# S7CAS-PLEIADES-CARTE-MERE_P20_FPGA-Decou.net
KiCad netlist of a schematic drawn in Altium Designer
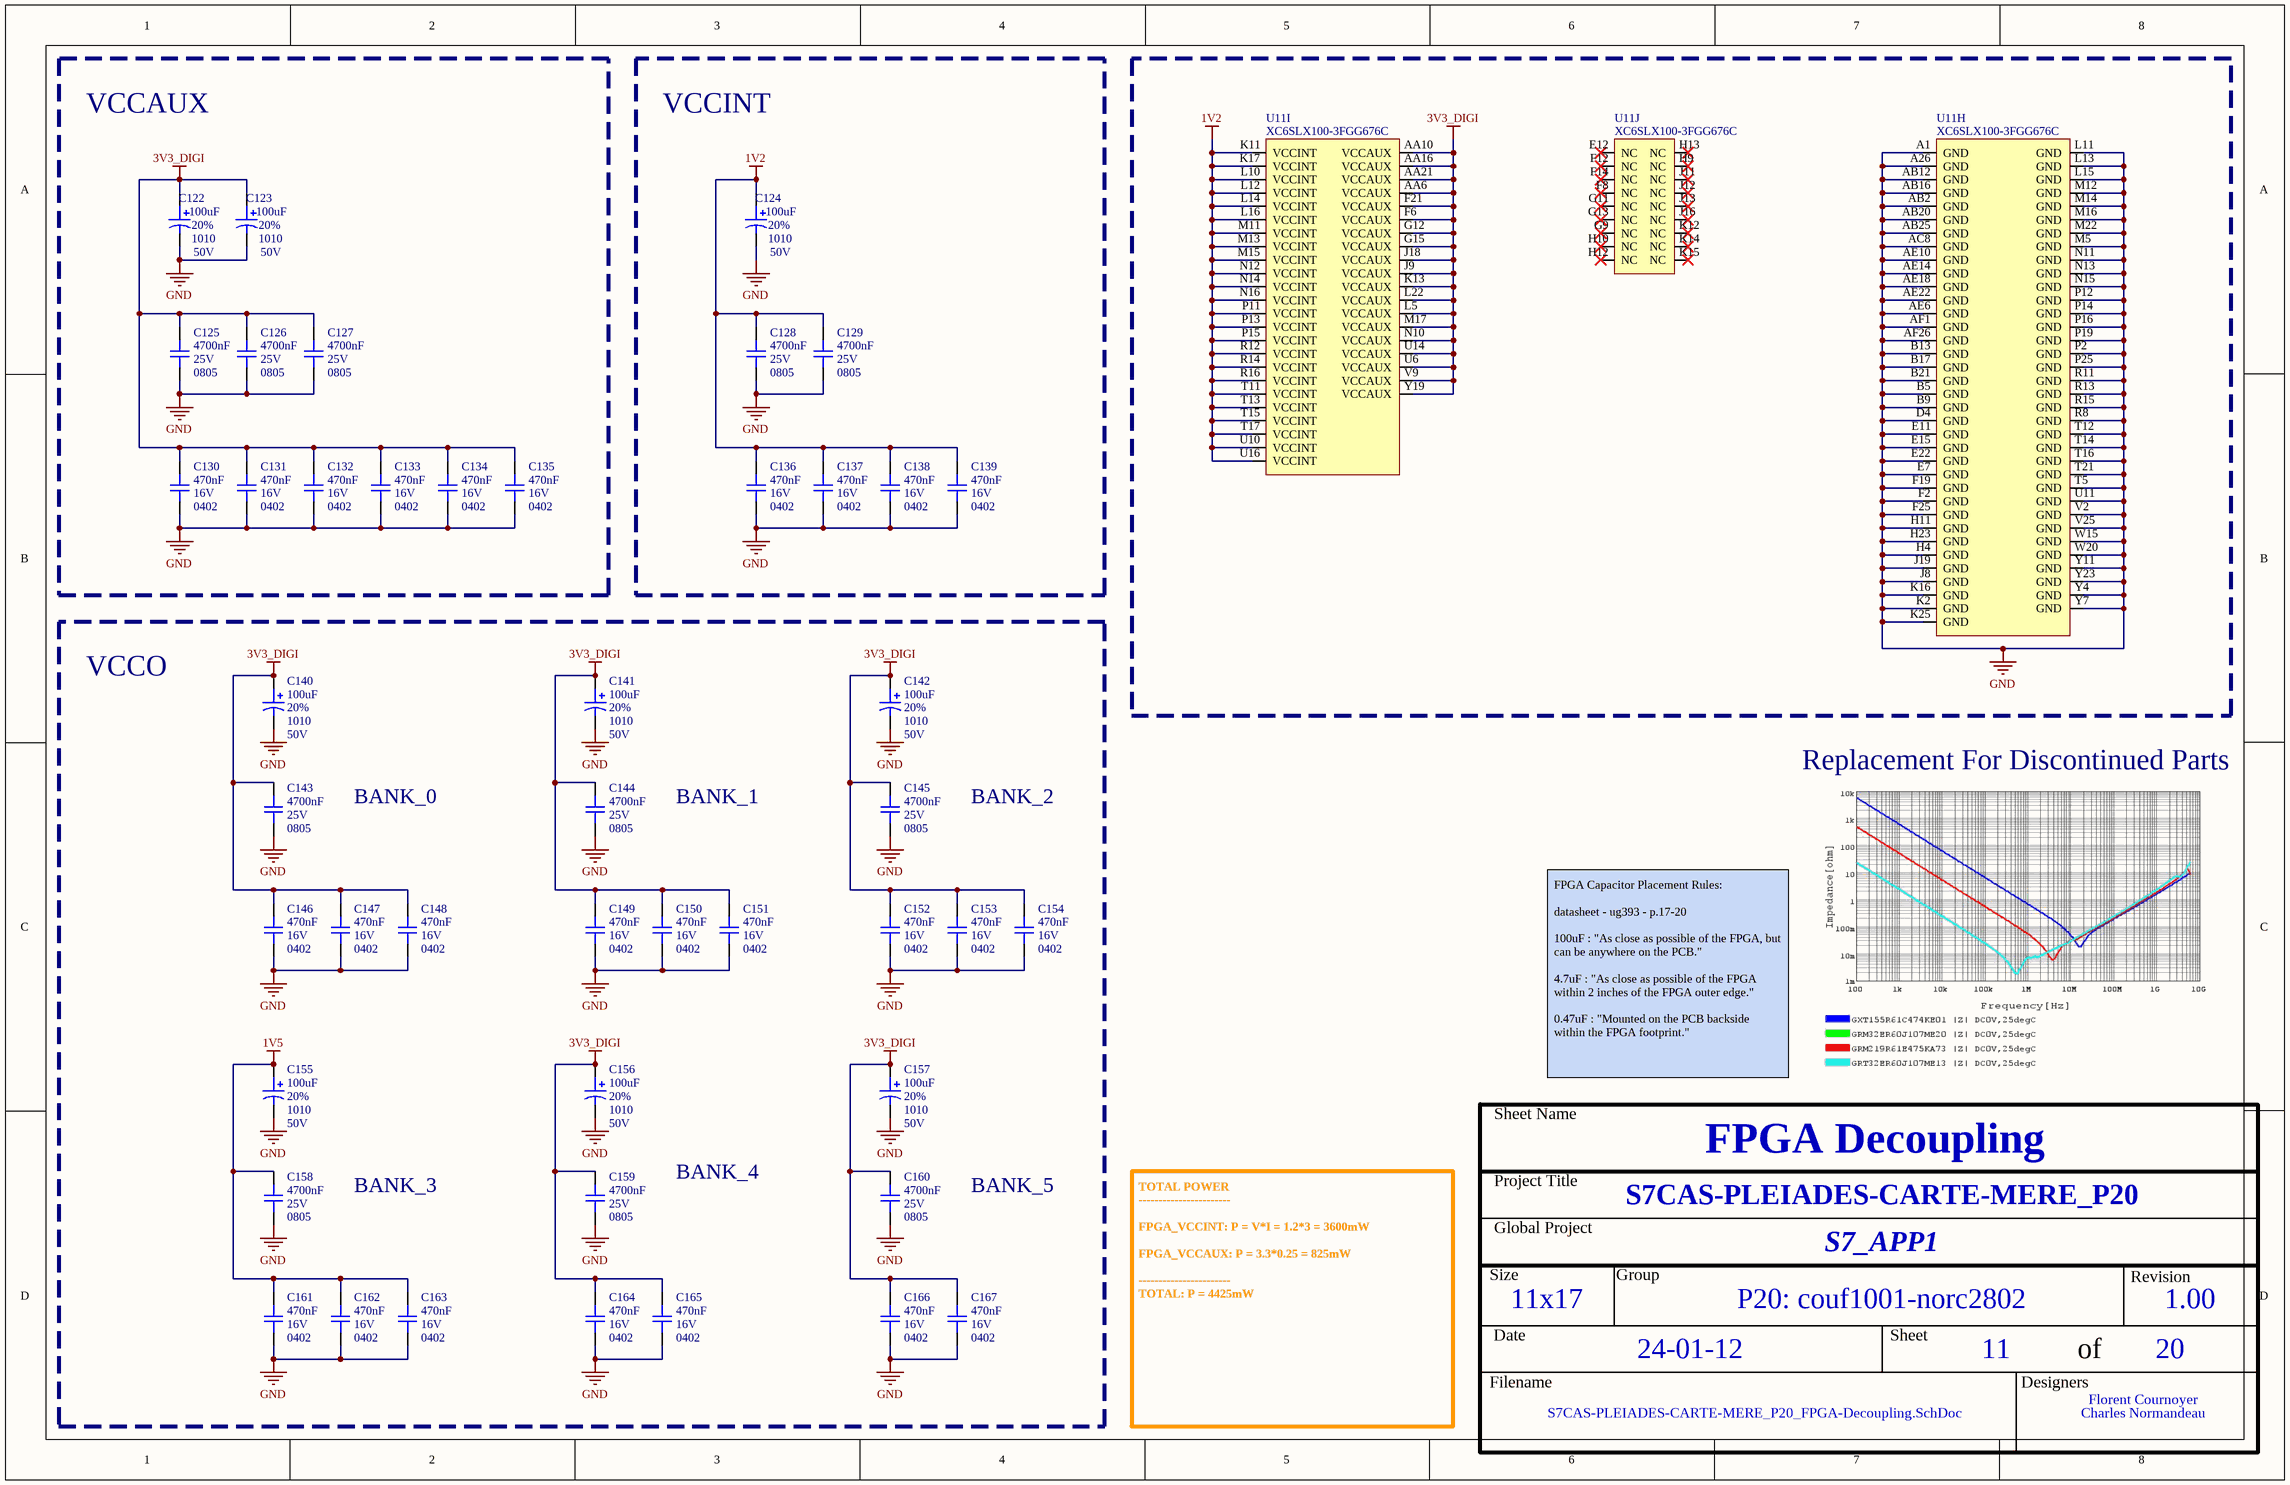
[diagram p0: S7CAS-PLEIADES-CARTE-MERE_P20_FPGA-Decoupling.SchDoc]

(export (version "E")
  (design (tool "Eeschema 10.0.6"))
  (components
    (comp (ref "C122")
      (value "100uF")
      (footprint "CAP_ALU_1010_vishay")
      (description "CAP - ALU 100uF 20% 50V - 1010")
      (fields
        (field (name "MFG") "Vishay Dale")
        (field (name "MFG PART NUMBER") "MAL215099101E3")
        (field (name "VOLTAGE") "50V")
        (field (name "PACKAGE") "1010")
        (field (name "PRECISION") "20%")
        (field (name "CREATEDBY") "Jonathan Bouchard")
      )
      (libsource (lib "S7CAS_LIB2023") (part "CAP_ALU_MAL215099101E3"))
    )
    (comp (ref "C123")
      (value "100uF")
      (footprint "CAP_ALU_1010_vishay")
      (description "CAP - ALU 100uF 20% 50V - 1010")
      (fields
        (field (name "MFG") "Vishay Dale")
        (field (name "MFG PART NUMBER") "MAL215099101E3")
        (field (name "VOLTAGE") "50V")
        (field (name "PACKAGE") "1010")
        (field (name "PRECISION") "20%")
        (field (name "CREATEDBY") "Jonathan Bouchard")
      )
      (libsource (lib "S7CAS_LIB2023") (part "CAP_ALU_MAL215099101E3"))
    )
    (comp (ref "C124")
      (value "100uF")
      (footprint "CAP_ALU_1010_vishay")
      (description "CAP - ALU 100uF 20% 50V - 1010")
      (fields
        (field (name "MFG") "Vishay Dale")
        (field (name "MFG PART NUMBER") "MAL215099101E3")
        (field (name "VOLTAGE") "50V")
        (field (name "PACKAGE") "1010")
        (field (name "PRECISION") "20%")
        (field (name "CREATEDBY") "Jonathan Bouchard")
      )
      (libsource (lib "S7CAS_LIB2023") (part "CAP_ALU_MAL215099101E3"))
    )
    (comp (ref "C125")
      (value "4700nF")
      (footprint "CAP_0805")
      (description "CAP - 0805")
      (fields
        (field (name "MFG PART NUMBER") "GRM219R61E475KA73")
        (field (name "VOLTAGE") "25V")
        (field (name "PACKAGE") "0805")
        (field (name "CREATEDBY") "Jonathan Bouchard")
      )
      (libsource (lib "S7CAS_LIB2023") (part "CAP - 0805"))
    )
    (comp (ref "C126")
      (value "4700nF")
      (footprint "CAP_0805")
      (description "CAP - 0805")
      (fields
        (field (name "MFG PART NUMBER") "GRM219R61E475KA73")
        (field (name "VOLTAGE") "25V")
        (field (name "PACKAGE") "0805")
        (field (name "CREATEDBY") "Jonathan Bouchard")
      )
      (libsource (lib "S7CAS_LIB2023") (part "CAP - 0805"))
    )
    (comp (ref "C127")
      (value "4700nF")
      (footprint "CAP_0805")
      (description "CAP - 0805")
      (fields
        (field (name "MFG PART NUMBER") "GRM219R61E475KA73")
        (field (name "VOLTAGE") "25V")
        (field (name "PACKAGE") "0805")
        (field (name "CREATEDBY") "Jonathan Bouchard")
      )
      (libsource (lib "S7CAS_LIB2023") (part "CAP - 0805"))
    )
    (comp (ref "C128")
      (value "4700nF")
      (footprint "CAP_0805")
      (description "CAP - 0805")
      (fields
        (field (name "MFG PART NUMBER") "GRM219R61E475KA73")
        (field (name "VOLTAGE") "25V")
        (field (name "PACKAGE") "0805")
        (field (name "CREATEDBY") "Jonathan Bouchard")
      )
      (libsource (lib "S7CAS_LIB2023") (part "CAP - 0805"))
    )
    (comp (ref "C129")
      (value "4700nF")
      (footprint "CAP_0805")
      (description "CAP - 0805")
      (fields
        (field (name "MFG PART NUMBER") "GRM219R61E475KA73")
        (field (name "VOLTAGE") "25V")
        (field (name "PACKAGE") "0805")
        (field (name "CREATEDBY") "Jonathan Bouchard")
      )
      (libsource (lib "S7CAS_LIB2023") (part "CAP - 0805"))
    )
    (comp (ref "C130")
      (value "470nF")
      (footprint "CAP_0402")
      (description "CAP - 0402")
      (fields
        (field (name "MFG PART NUMBER") "GXT155R61C474KE01")
        (field (name "VOLTAGE") "16V")
        (field (name "PACKAGE") "0402")
        (field (name "CREATEDBY") "Jonathan Bouchard")
      )
      (libsource (lib "S7CAS_LIB2023") (part "CAP - 0402"))
    )
    (comp (ref "C131")
      (value "470nF")
      (footprint "CAP_0402")
      (description "CAP - 0402")
      (fields
        (field (name "MFG PART NUMBER") "GXT155R61C474KE01")
        (field (name "VOLTAGE") "16V")
        (field (name "PACKAGE") "0402")
        (field (name "CREATEDBY") "Jonathan Bouchard")
      )
      (libsource (lib "S7CAS_LIB2023") (part "CAP - 0402"))
    )
    (comp (ref "C132")
      (value "470nF")
      (footprint "CAP_0402")
      (description "CAP - 0402")
      (fields
        (field (name "MFG PART NUMBER") "GXT155R61C474KE01")
        (field (name "VOLTAGE") "16V")
        (field (name "PACKAGE") "0402")
        (field (name "CREATEDBY") "Jonathan Bouchard")
      )
      (libsource (lib "S7CAS_LIB2023") (part "CAP - 0402"))
    )
    (comp (ref "C133")
      (value "470nF")
      (footprint "CAP_0402")
      (description "CAP - 0402")
      (fields
        (field (name "MFG PART NUMBER") "GXT155R61C474KE01")
        (field (name "VOLTAGE") "16V")
        (field (name "PACKAGE") "0402")
        (field (name "CREATEDBY") "Jonathan Bouchard")
      )
      (libsource (lib "S7CAS_LIB2023") (part "CAP - 0402"))
    )
    (comp (ref "C134")
      (value "470nF")
      (footprint "CAP_0402")
      (description "CAP - 0402")
      (fields
        (field (name "MFG PART NUMBER") "GXT155R61C474KE01")
        (field (name "VOLTAGE") "16V")
        (field (name "PACKAGE") "0402")
        (field (name "CREATEDBY") "Jonathan Bouchard")
      )
      (libsource (lib "S7CAS_LIB2023") (part "CAP - 0402"))
    )
    (comp (ref "C135")
      (value "470nF")
      (footprint "CAP_0402")
      (description "CAP - 0402")
      (fields
        (field (name "MFG PART NUMBER") "GXT155R61C474KE01")
        (field (name "VOLTAGE") "16V")
        (field (name "PACKAGE") "0402")
        (field (name "CREATEDBY") "Jonathan Bouchard")
      )
      (libsource (lib "S7CAS_LIB2023") (part "CAP - 0402"))
    )
    (comp (ref "C136")
      (value "470nF")
      (footprint "CAP_0402")
      (description "CAP - 0402")
      (fields
        (field (name "MFG PART NUMBER") "GXT155R61C474KE01")
        (field (name "VOLTAGE") "16V")
        (field (name "PACKAGE") "0402")
        (field (name "CREATEDBY") "Jonathan Bouchard")
      )
      (libsource (lib "S7CAS_LIB2023") (part "CAP - 0402"))
    )
    (comp (ref "C137")
      (value "470nF")
      (footprint "CAP_0402")
      (description "CAP - 0402")
      (fields
        (field (name "MFG PART NUMBER") "GXT155R61C474KE01")
        (field (name "VOLTAGE") "16V")
        (field (name "PACKAGE") "0402")
        (field (name "CREATEDBY") "Jonathan Bouchard")
      )
      (libsource (lib "S7CAS_LIB2023") (part "CAP - 0402"))
    )
    (comp (ref "C138")
      (value "470nF")
      (footprint "CAP_0402")
      (description "CAP - 0402")
      (fields
        (field (name "MFG PART NUMBER") "GXT155R61C474KE01")
        (field (name "VOLTAGE") "16V")
        (field (name "PACKAGE") "0402")
        (field (name "CREATEDBY") "Jonathan Bouchard")
      )
      (libsource (lib "S7CAS_LIB2023") (part "CAP - 0402"))
    )
    (comp (ref "C139")
      (value "470nF")
      (footprint "CAP_0402")
      (description "CAP - 0402")
      (fields
        (field (name "MFG PART NUMBER") "GXT155R61C474KE01")
        (field (name "VOLTAGE") "16V")
        (field (name "PACKAGE") "0402")
        (field (name "CREATEDBY") "Jonathan Bouchard")
      )
      (libsource (lib "S7CAS_LIB2023") (part "CAP - 0402"))
    )
    (comp (ref "C140")
      (value "100uF")
      (footprint "CAP_ALU_1010_vishay")
      (description "CAP - ALU 100uF 20% 50V - 1010")
      (fields
        (field (name "MFG") "Vishay Dale")
        (field (name "MFG PART NUMBER") "MAL215099101E3")
        (field (name "VOLTAGE") "50V")
        (field (name "PACKAGE") "1010")
        (field (name "PRECISION") "20%")
        (field (name "CREATEDBY") "Jonathan Bouchard")
      )
      (libsource (lib "S7CAS_LIB2023") (part "CAP_ALU_MAL215099101E3"))
    )
    (comp (ref "C141")
      (value "100uF")
      (footprint "CAP_ALU_1010_vishay")
      (description "CAP - ALU 100uF 20% 50V - 1010")
      (fields
        (field (name "MFG") "Vishay Dale")
        (field (name "MFG PART NUMBER") "MAL215099101E3")
        (field (name "VOLTAGE") "50V")
        (field (name "PACKAGE") "1010")
        (field (name "PRECISION") "20%")
        (field (name "CREATEDBY") "Jonathan Bouchard")
      )
      (libsource (lib "S7CAS_LIB2023") (part "CAP_ALU_MAL215099101E3"))
    )
    (comp (ref "C142")
      (value "100uF")
      (footprint "CAP_ALU_1010_vishay")
      (description "CAP - ALU 100uF 20% 50V - 1010")
      (fields
        (field (name "MFG") "Vishay Dale")
        (field (name "MFG PART NUMBER") "MAL215099101E3")
        (field (name "VOLTAGE") "50V")
        (field (name "PACKAGE") "1010")
        (field (name "PRECISION") "20%")
        (field (name "CREATEDBY") "Jonathan Bouchard")
      )
      (libsource (lib "S7CAS_LIB2023") (part "CAP_ALU_MAL215099101E3"))
    )
    (comp (ref "C143")
      (value "4700nF")
      (footprint "CAP_0805")
      (description "CAP - 0805")
      (fields
        (field (name "MFG PART NUMBER") "GRM219R61E475KA73")
        (field (name "VOLTAGE") "25V")
        (field (name "PACKAGE") "0805")
        (field (name "CREATEDBY") "Jonathan Bouchard")
      )
      (libsource (lib "S7CAS_LIB2023") (part "CAP - 0805"))
    )
    (comp (ref "C144")
      (value "4700nF")
      (footprint "CAP_0805")
      (description "CAP - 0805")
      (fields
        (field (name "MFG PART NUMBER") "GRM219R61E475KA73")
        (field (name "VOLTAGE") "25V")
        (field (name "PACKAGE") "0805")
        (field (name "CREATEDBY") "Jonathan Bouchard")
      )
      (libsource (lib "S7CAS_LIB2023") (part "CAP - 0805"))
    )
    (comp (ref "C145")
      (value "4700nF")
      (footprint "CAP_0805")
      (description "CAP - 0805")
      (fields
        (field (name "MFG PART NUMBER") "GRM219R61E475KA73")
        (field (name "VOLTAGE") "25V")
        (field (name "PACKAGE") "0805")
        (field (name "CREATEDBY") "Jonathan Bouchard")
      )
      (libsource (lib "S7CAS_LIB2023") (part "CAP - 0805"))
    )
    (comp (ref "C146")
      (value "470nF")
      (footprint "CAP_0402")
      (description "CAP - 0402")
      (fields
        (field (name "MFG PART NUMBER") "GXT155R61C474KE01")
        (field (name "VOLTAGE") "16V")
        (field (name "PACKAGE") "0402")
        (field (name "CREATEDBY") "Jonathan Bouchard")
      )
      (libsource (lib "S7CAS_LIB2023") (part "CAP - 0402"))
    )
    (comp (ref "C147")
      (value "470nF")
      (footprint "CAP_0402")
      (description "CAP - 0402")
      (fields
        (field (name "MFG PART NUMBER") "GXT155R61C474KE01")
        (field (name "VOLTAGE") "16V")
        (field (name "PACKAGE") "0402")
        (field (name "CREATEDBY") "Jonathan Bouchard")
      )
      (libsource (lib "S7CAS_LIB2023") (part "CAP - 0402"))
    )
    (comp (ref "C148")
      (value "470nF")
      (footprint "CAP_0402")
      (description "CAP - 0402")
      (fields
        (field (name "MFG PART NUMBER") "GXT155R61C474KE01")
        (field (name "VOLTAGE") "16V")
        (field (name "PACKAGE") "0402")
        (field (name "CREATEDBY") "Jonathan Bouchard")
      )
      (libsource (lib "S7CAS_LIB2023") (part "CAP - 0402"))
    )
    (comp (ref "C149")
      (value "470nF")
      (footprint "CAP_0402")
      (description "CAP - 0402")
      (fields
        (field (name "MFG PART NUMBER") "GXT155R61C474KE01")
        (field (name "VOLTAGE") "16V")
        (field (name "PACKAGE") "0402")
        (field (name "CREATEDBY") "Jonathan Bouchard")
      )
      (libsource (lib "S7CAS_LIB2023") (part "CAP - 0402"))
    )
    (comp (ref "C150")
      (value "470nF")
      (footprint "CAP_0402")
      (description "CAP - 0402")
      (fields
        (field (name "MFG PART NUMBER") "GXT155R61C474KE01")
        (field (name "VOLTAGE") "16V")
        (field (name "PACKAGE") "0402")
        (field (name "CREATEDBY") "Jonathan Bouchard")
      )
      (libsource (lib "S7CAS_LIB2023") (part "CAP - 0402"))
    )
    (comp (ref "C151")
      (value "470nF")
      (footprint "CAP_0402")
      (description "CAP - 0402")
      (fields
        (field (name "MFG PART NUMBER") "GXT155R61C474KE01")
        (field (name "VOLTAGE") "16V")
        (field (name "PACKAGE") "0402")
        (field (name "CREATEDBY") "Jonathan Bouchard")
      )
      (libsource (lib "S7CAS_LIB2023") (part "CAP - 0402"))
    )
    (comp (ref "C152")
      (value "470nF")
      (footprint "CAP_0402")
      (description "CAP - 0402")
      (fields
        (field (name "MFG PART NUMBER") "GXT155R61C474KE01")
        (field (name "VOLTAGE") "16V")
        (field (name "PACKAGE") "0402")
        (field (name "CREATEDBY") "Jonathan Bouchard")
      )
      (libsource (lib "S7CAS_LIB2023") (part "CAP - 0402"))
    )
    (comp (ref "C153")
      (value "470nF")
      (footprint "CAP_0402")
      (description "CAP - 0402")
      (fields
        (field (name "MFG PART NUMBER") "GXT155R61C474KE01")
        (field (name "VOLTAGE") "16V")
        (field (name "PACKAGE") "0402")
        (field (name "CREATEDBY") "Jonathan Bouchard")
      )
      (libsource (lib "S7CAS_LIB2023") (part "CAP - 0402"))
    )
    (comp (ref "C154")
      (value "470nF")
      (footprint "CAP_0402")
      (description "CAP - 0402")
      (fields
        (field (name "MFG PART NUMBER") "GXT155R61C474KE01")
        (field (name "VOLTAGE") "16V")
        (field (name "PACKAGE") "0402")
        (field (name "CREATEDBY") "Jonathan Bouchard")
      )
      (libsource (lib "S7CAS_LIB2023") (part "CAP - 0402"))
    )
    (comp (ref "C155")
      (value "100uF")
      (footprint "CAP_ALU_1010_vishay")
      (description "CAP - ALU 100uF 20% 50V - 1010")
      (fields
        (field (name "MFG") "Vishay Dale")
        (field (name "MFG PART NUMBER") "MAL215099101E3")
        (field (name "VOLTAGE") "50V")
        (field (name "PACKAGE") "1010")
        (field (name "PRECISION") "20%")
        (field (name "CREATEDBY") "Jonathan Bouchard")
      )
      (libsource (lib "S7CAS_LIB2023") (part "CAP_ALU_MAL215099101E3"))
    )
    (comp (ref "C156")
      (value "100uF")
      (footprint "CAP_ALU_1010_vishay")
      (description "CAP - ALU 100uF 20% 50V - 1010")
      (fields
        (field (name "MFG") "Vishay Dale")
        (field (name "MFG PART NUMBER") "MAL215099101E3")
        (field (name "VOLTAGE") "50V")
        (field (name "PACKAGE") "1010")
        (field (name "PRECISION") "20%")
        (field (name "CREATEDBY") "Jonathan Bouchard")
      )
      (libsource (lib "S7CAS_LIB2023") (part "CAP_ALU_MAL215099101E3"))
    )
    (comp (ref "C157")
      (value "100uF")
      (footprint "CAP_ALU_1010_vishay")
      (description "CAP - ALU 100uF 20% 50V - 1010")
      (fields
        (field (name "MFG") "Vishay Dale")
        (field (name "MFG PART NUMBER") "MAL215099101E3")
        (field (name "VOLTAGE") "50V")
        (field (name "PACKAGE") "1010")
        (field (name "PRECISION") "20%")
        (field (name "CREATEDBY") "Jonathan Bouchard")
      )
      (libsource (lib "S7CAS_LIB2023") (part "CAP_ALU_MAL215099101E3"))
    )
    (comp (ref "C158")
      (value "4700nF")
      (footprint "CAP_0805")
      (description "CAP - 0805")
      (fields
        (field (name "MFG PART NUMBER") "GRM219R61E475KA73")
        (field (name "VOLTAGE") "25V")
        (field (name "PACKAGE") "0805")
        (field (name "CREATEDBY") "Jonathan Bouchard")
      )
      (libsource (lib "S7CAS_LIB2023") (part "CAP - 0805"))
    )
    (comp (ref "C159")
      (value "4700nF")
      (footprint "CAP_0805")
      (description "CAP - 0805")
      (fields
        (field (name "MFG PART NUMBER") "GRM219R61E475KA73")
        (field (name "VOLTAGE") "25V")
        (field (name "PACKAGE") "0805")
        (field (name "CREATEDBY") "Jonathan Bouchard")
      )
      (libsource (lib "S7CAS_LIB2023") (part "CAP - 0805"))
    )
    (comp (ref "C160")
      (value "4700nF")
      (footprint "CAP_0805")
      (description "CAP - 0805")
      (fields
        (field (name "MFG PART NUMBER") "GRM219R61E475KA73")
        (field (name "VOLTAGE") "25V")
        (field (name "PACKAGE") "0805")
        (field (name "CREATEDBY") "Jonathan Bouchard")
      )
      (libsource (lib "S7CAS_LIB2023") (part "CAP - 0805"))
    )
    (comp (ref "C161")
      (value "470nF")
      (footprint "CAP_0402")
      (description "CAP - 0402")
      (fields
        (field (name "MFG PART NUMBER") "GXT155R61C474KE01")
        (field (name "VOLTAGE") "16V")
        (field (name "PACKAGE") "0402")
        (field (name "CREATEDBY") "Jonathan Bouchard")
      )
      (libsource (lib "S7CAS_LIB2023") (part "CAP - 0402"))
    )
    (comp (ref "C162")
      (value "470nF")
      (footprint "CAP_0402")
      (description "CAP - 0402")
      (fields
        (field (name "MFG PART NUMBER") "GXT155R61C474KE01")
        (field (name "VOLTAGE") "16V")
        (field (name "PACKAGE") "0402")
        (field (name "CREATEDBY") "Jonathan Bouchard")
      )
      (libsource (lib "S7CAS_LIB2023") (part "CAP - 0402"))
    )
    (comp (ref "C163")
      (value "470nF")
      (footprint "CAP_0402")
      (description "CAP - 0402")
      (fields
        (field (name "MFG PART NUMBER") "GXT155R61C474KE01")
        (field (name "VOLTAGE") "16V")
        (field (name "PACKAGE") "0402")
        (field (name "CREATEDBY") "Jonathan Bouchard")
      )
      (libsource (lib "S7CAS_LIB2023") (part "CAP - 0402"))
    )
    (comp (ref "C164")
      (value "470nF")
      (footprint "CAP_0402")
      (description "CAP - 0402")
      (fields
        (field (name "MFG PART NUMBER") "GXT155R61C474KE01")
        (field (name "VOLTAGE") "16V")
        (field (name "PACKAGE") "0402")
        (field (name "CREATEDBY") "Jonathan Bouchard")
      )
      (libsource (lib "S7CAS_LIB2023") (part "CAP - 0402"))
    )
    (comp (ref "C165")
      (value "470nF")
      (footprint "CAP_0402")
      (description "CAP - 0402")
      (fields
        (field (name "MFG PART NUMBER") "GXT155R61C474KE01")
        (field (name "VOLTAGE") "16V")
        (field (name "PACKAGE") "0402")
        (field (name "CREATEDBY") "Jonathan Bouchard")
      )
      (libsource (lib "S7CAS_LIB2023") (part "CAP - 0402"))
    )
    (comp (ref "C166")
      (value "470nF")
      (footprint "CAP_0402")
      (description "CAP - 0402")
      (fields
        (field (name "MFG PART NUMBER") "GXT155R61C474KE01")
        (field (name "VOLTAGE") "16V")
        (field (name "PACKAGE") "0402")
        (field (name "CREATEDBY") "Jonathan Bouchard")
      )
      (libsource (lib "S7CAS_LIB2023") (part "CAP - 0402"))
    )
    (comp (ref "C167")
      (value "470nF")
      (footprint "CAP_0402")
      (description "CAP - 0402")
      (fields
        (field (name "MFG PART NUMBER") "GXT155R61C474KE01")
        (field (name "VOLTAGE") "16V")
        (field (name "PACKAGE") "0402")
        (field (name "CREATEDBY") "Jonathan Bouchard")
      )
      (libsource (lib "S7CAS_LIB2023") (part "CAP - 0402"))
    )
    (comp (ref "U11")
      (value "XC6SLX100-3FGG676C")
      (footprint "FPGA_XILINX_FGG676")
      (description "FPGA - XILINX SPARTAN 6 480 I/O - BGA-676")
      (fields
        (field (name "VOLTAGE") "1.14 V ~ 1.26 V")
        (field (name "MFG") "Xilinx")
        (field (name "CREATEDBY") "Jonathan Bouchard")
      )
      (libsource (lib "S7CAS_LIB2023") (part "FPGA_XC6SLX100-3FGG676C"))
    )
  )
  (nets
    (net (code "1") (name "1V2") (class "Default")
      (node (ref "C124") (pin "1") (pinfunction "1_1") (pintype "passive"))
      (node (ref "C128") (pin "2") (pinfunction "2_2") (pintype "passive"))
      (node (ref "C129") (pin "2") (pinfunction "2_2") (pintype "passive"))
      (node (ref "C136") (pin "2") (pinfunction "2_2") (pintype "passive"))
      (node (ref "C137") (pin "2") (pinfunction "2_2") (pintype "passive"))
      (node (ref "C138") (pin "2") (pinfunction "2_2") (pintype "passive"))
      (node (ref "C139") (pin "2") (pinfunction "2_2") (pintype "passive"))
      (node (ref "U11") (pin "K11") (pinfunction "VCCINT_K11") (pintype "passive"))
      (node (ref "U11") (pin "K17") (pinfunction "VCCINT_K17") (pintype "passive"))
      (node (ref "U11") (pin "L10") (pinfunction "VCCINT_L10") (pintype "passive"))
      (node (ref "U11") (pin "L12") (pinfunction "VCCINT_L12") (pintype "passive"))
      (node (ref "U11") (pin "L14") (pinfunction "VCCINT_L14") (pintype "passive"))
      (node (ref "U11") (pin "L16") (pinfunction "VCCINT_L16") (pintype "passive"))
      (node (ref "U11") (pin "M11") (pinfunction "VCCINT_M11") (pintype "passive"))
      (node (ref "U11") (pin "M13") (pinfunction "VCCINT_M13") (pintype "passive"))
      (node (ref "U11") (pin "M15") (pinfunction "VCCINT_M15") (pintype "passive"))
      (node (ref "U11") (pin "N12") (pinfunction "VCCINT_N12") (pintype "passive"))
      (node (ref "U11") (pin "N14") (pinfunction "VCCINT_N14") (pintype "passive"))
      (node (ref "U11") (pin "N16") (pinfunction "VCCINT_N16") (pintype "passive"))
      (node (ref "U11") (pin "P11") (pinfunction "VCCINT_P11") (pintype "passive"))
      (node (ref "U11") (pin "P13") (pinfunction "VCCINT_P13") (pintype "passive"))
      (node (ref "U11") (pin "P15") (pinfunction "VCCINT_P15") (pintype "passive"))
      (node (ref "U11") (pin "R12") (pinfunction "VCCINT_R12") (pintype "passive"))
      (node (ref "U11") (pin "R14") (pinfunction "VCCINT_R14") (pintype "passive"))
      (node (ref "U11") (pin "R16") (pinfunction "VCCINT_R16") (pintype "passive"))
      (node (ref "U11") (pin "T11") (pinfunction "VCCINT_T11") (pintype "passive"))
      (node (ref "U11") (pin "T13") (pinfunction "VCCINT_T13") (pintype "passive"))
      (node (ref "U11") (pin "T15") (pinfunction "VCCINT_T15") (pintype "passive"))
      (node (ref "U11") (pin "T17") (pinfunction "VCCINT_T17") (pintype "passive"))
      (node (ref "U11") (pin "U10") (pinfunction "VCCINT_U10") (pintype "passive"))
      (node (ref "U11") (pin "U16") (pinfunction "VCCINT_U16") (pintype "passive"))
    )
    (net (code "2") (name "1V5") (class "Default")
      (node (ref "C155") (pin "1") (pinfunction "1_1") (pintype "passive"))
      (node (ref "C158") (pin "2") (pinfunction "2_2") (pintype "passive"))
      (node (ref "C161") (pin "2") (pinfunction "2_2") (pintype "passive"))
      (node (ref "C162") (pin "2") (pinfunction "2_2") (pintype "passive"))
      (node (ref "C163") (pin "2") (pinfunction "2_2") (pintype "passive"))
    )
    (net (code "3") (name "3V3_DIGI") (class "Default")
      (node (ref "C122") (pin "1") (pinfunction "1_1") (pintype "passive"))
      (node (ref "C123") (pin "1") (pinfunction "1_1") (pintype "passive"))
      (node (ref "C125") (pin "2") (pinfunction "2_2") (pintype "passive"))
      (node (ref "C126") (pin "2") (pinfunction "2_2") (pintype "passive"))
      (node (ref "C127") (pin "2") (pinfunction "2_2") (pintype "passive"))
      (node (ref "C130") (pin "2") (pinfunction "2_2") (pintype "passive"))
      (node (ref "C131") (pin "2") (pinfunction "2_2") (pintype "passive"))
      (node (ref "C132") (pin "2") (pinfunction "2_2") (pintype "passive"))
      (node (ref "C133") (pin "2") (pinfunction "2_2") (pintype "passive"))
      (node (ref "C134") (pin "2") (pinfunction "2_2") (pintype "passive"))
      (node (ref "C135") (pin "2") (pinfunction "2_2") (pintype "passive"))
      (node (ref "C140") (pin "1") (pinfunction "1_1") (pintype "passive"))
      (node (ref "C141") (pin "1") (pinfunction "1_1") (pintype "passive"))
      (node (ref "C142") (pin "1") (pinfunction "1_1") (pintype "passive"))
      (node (ref "C143") (pin "2") (pinfunction "2_2") (pintype "passive"))
      (node (ref "C144") (pin "2") (pinfunction "2_2") (pintype "passive"))
      (node (ref "C145") (pin "2") (pinfunction "2_2") (pintype "passive"))
      (node (ref "C146") (pin "2") (pinfunction "2_2") (pintype "passive"))
      (node (ref "C147") (pin "2") (pinfunction "2_2") (pintype "passive"))
      (node (ref "C148") (pin "2") (pinfunction "2_2") (pintype "passive"))
      (node (ref "C149") (pin "2") (pinfunction "2_2") (pintype "passive"))
      (node (ref "C150") (pin "2") (pinfunction "2_2") (pintype "passive"))
      (node (ref "C151") (pin "2") (pinfunction "2_2") (pintype "passive"))
      (node (ref "C152") (pin "2") (pinfunction "2_2") (pintype "passive"))
      (node (ref "C153") (pin "2") (pinfunction "2_2") (pintype "passive"))
      (node (ref "C154") (pin "2") (pinfunction "2_2") (pintype "passive"))
      (node (ref "C156") (pin "1") (pinfunction "1_1") (pintype "passive"))
      (node (ref "C157") (pin "1") (pinfunction "1_1") (pintype "passive"))
      (node (ref "C159") (pin "2") (pinfunction "2_2") (pintype "passive"))
      (node (ref "C160") (pin "2") (pinfunction "2_2") (pintype "passive"))
      (node (ref "C164") (pin "2") (pinfunction "2_2") (pintype "passive"))
      (node (ref "C165") (pin "2") (pinfunction "2_2") (pintype "passive"))
      (node (ref "C166") (pin "2") (pinfunction "2_2") (pintype "passive"))
      (node (ref "C167") (pin "2") (pinfunction "2_2") (pintype "passive"))
      (node (ref "U11") (pin "AA10") (pinfunction "VCCAUX_AA10") (pintype "passive"))
      (node (ref "U11") (pin "AA16") (pinfunction "VCCAUX_AA16") (pintype "passive"))
      (node (ref "U11") (pin "AA21") (pinfunction "VCCAUX_AA21") (pintype "passive"))
      (node (ref "U11") (pin "AA6") (pinfunction "VCCAUX_AA6") (pintype "passive"))
      (node (ref "U11") (pin "F21") (pinfunction "VCCAUX_F21") (pintype "passive"))
      (node (ref "U11") (pin "F6") (pinfunction "VCCAUX_F6") (pintype "passive"))
      (node (ref "U11") (pin "G12") (pinfunction "VCCAUX_G12") (pintype "passive"))
      (node (ref "U11") (pin "G15") (pinfunction "VCCAUX_G15") (pintype "passive"))
      (node (ref "U11") (pin "J18") (pinfunction "VCCAUX_J18") (pintype "passive"))
      (node (ref "U11") (pin "J9") (pinfunction "VCCAUX_J9") (pintype "passive"))
      (node (ref "U11") (pin "K13") (pinfunction "VCCAUX_K13") (pintype "passive"))
      (node (ref "U11") (pin "L22") (pinfunction "VCCAUX_L22") (pintype "passive"))
      (node (ref "U11") (pin "L5") (pinfunction "VCCAUX_L5") (pintype "passive"))
      (node (ref "U11") (pin "M17") (pinfunction "VCCAUX_M17") (pintype "passive"))
      (node (ref "U11") (pin "N10") (pinfunction "VCCAUX_N10") (pintype "passive"))
      (node (ref "U11") (pin "U14") (pinfunction "VCCAUX_U14") (pintype "passive"))
      (node (ref "U11") (pin "U6") (pinfunction "VCCAUX_U6") (pintype "passive"))
      (node (ref "U11") (pin "V9") (pinfunction "VCCAUX_V9") (pintype "passive"))
      (node (ref "U11") (pin "Y19") (pinfunction "VCCAUX_Y19") (pintype "passive"))
    )
    (net (code "4") (name "GND") (class "Default")
      (node (ref "C122") (pin "2") (pinfunction "2_2") (pintype "passive"))
      (node (ref "C123") (pin "2") (pinfunction "2_2") (pintype "passive"))
      (node (ref "C124") (pin "2") (pinfunction "2_2") (pintype "passive"))
      (node (ref "C125") (pin "1") (pinfunction "1_1") (pintype "passive"))
      (node (ref "C126") (pin "1") (pinfunction "1_1") (pintype "passive"))
      (node (ref "C127") (pin "1") (pinfunction "1_1") (pintype "passive"))
      (node (ref "C128") (pin "1") (pinfunction "1_1") (pintype "passive"))
      (node (ref "C129") (pin "1") (pinfunction "1_1") (pintype "passive"))
      (node (ref "C130") (pin "1") (pinfunction "1_1") (pintype "passive"))
      (node (ref "C131") (pin "1") (pinfunction "1_1") (pintype "passive"))
      (node (ref "C132") (pin "1") (pinfunction "1_1") (pintype "passive"))
      (node (ref "C133") (pin "1") (pinfunction "1_1") (pintype "passive"))
      (node (ref "C134") (pin "1") (pinfunction "1_1") (pintype "passive"))
      (node (ref "C135") (pin "1") (pinfunction "1_1") (pintype "passive"))
      (node (ref "C136") (pin "1") (pinfunction "1_1") (pintype "passive"))
      (node (ref "C137") (pin "1") (pinfunction "1_1") (pintype "passive"))
      (node (ref "C138") (pin "1") (pinfunction "1_1") (pintype "passive"))
      (node (ref "C139") (pin "1") (pinfunction "1_1") (pintype "passive"))
      (node (ref "C140") (pin "2") (pinfunction "2_2") (pintype "passive"))
      (node (ref "C141") (pin "2") (pinfunction "2_2") (pintype "passive"))
      (node (ref "C142") (pin "2") (pinfunction "2_2") (pintype "passive"))
      (node (ref "C143") (pin "1") (pinfunction "1_1") (pintype "passive"))
      (node (ref "C144") (pin "1") (pinfunction "1_1") (pintype "passive"))
      (node (ref "C145") (pin "1") (pinfunction "1_1") (pintype "passive"))
      (node (ref "C146") (pin "1") (pinfunction "1_1") (pintype "passive"))
      (node (ref "C147") (pin "1") (pinfunction "1_1") (pintype "passive"))
      (node (ref "C148") (pin "1") (pinfunction "1_1") (pintype "passive"))
      (node (ref "C149") (pin "1") (pinfunction "1_1") (pintype "passive"))
      (node (ref "C150") (pin "1") (pinfunction "1_1") (pintype "passive"))
      (node (ref "C151") (pin "1") (pinfunction "1_1") (pintype "passive"))
      (node (ref "C152") (pin "1") (pinfunction "1_1") (pintype "passive"))
      (node (ref "C153") (pin "1") (pinfunction "1_1") (pintype "passive"))
      (node (ref "C154") (pin "1") (pinfunction "1_1") (pintype "passive"))
      (node (ref "C155") (pin "2") (pinfunction "2_2") (pintype "passive"))
      (node (ref "C156") (pin "2") (pinfunction "2_2") (pintype "passive"))
      (node (ref "C157") (pin "2") (pinfunction "2_2") (pintype "passive"))
      (node (ref "C158") (pin "1") (pinfunction "1_1") (pintype "passive"))
      (node (ref "C159") (pin "1") (pinfunction "1_1") (pintype "passive"))
      (node (ref "C160") (pin "1") (pinfunction "1_1") (pintype "passive"))
      (node (ref "C161") (pin "1") (pinfunction "1_1") (pintype "passive"))
      (node (ref "C162") (pin "1") (pinfunction "1_1") (pintype "passive"))
      (node (ref "C163") (pin "1") (pinfunction "1_1") (pintype "passive"))
      (node (ref "C164") (pin "1") (pinfunction "1_1") (pintype "passive"))
      (node (ref "C165") (pin "1") (pinfunction "1_1") (pintype "passive"))
      (node (ref "C166") (pin "1") (pinfunction "1_1") (pintype "passive"))
      (node (ref "C167") (pin "1") (pinfunction "1_1") (pintype "passive"))
      (node (ref "U11") (pin "A1") (pinfunction "GND_A1") (pintype "passive"))
      (node (ref "U11") (pin "A26") (pinfunction "GND_A26") (pintype "passive"))
      (node (ref "U11") (pin "AB12") (pinfunction "GND_AB12") (pintype "passive"))
      (node (ref "U11") (pin "AB16") (pinfunction "GND_AB16") (pintype "passive"))
      (node (ref "U11") (pin "AB2") (pinfunction "GND_AB2") (pintype "passive"))
      (node (ref "U11") (pin "AB20") (pinfunction "GND_AB20") (pintype "passive"))
      (node (ref "U11") (pin "AB25") (pinfunction "GND_AB25") (pintype "passive"))
      (node (ref "U11") (pin "AC8") (pinfunction "GND_AC8") (pintype "passive"))
      (node (ref "U11") (pin "AE10") (pinfunction "GND_AE10") (pintype "passive"))
      (node (ref "U11") (pin "AE14") (pinfunction "GND_AE14") (pintype "passive"))
      (node (ref "U11") (pin "AE18") (pinfunction "GND_AE18") (pintype "passive"))
      (node (ref "U11") (pin "AE22") (pinfunction "GND_AE22") (pintype "passive"))
      (node (ref "U11") (pin "AE6") (pinfunction "GND_AE6") (pintype "passive"))
      (node (ref "U11") (pin "AF1") (pinfunction "GND_AF1") (pintype "passive"))
      (node (ref "U11") (pin "AF26") (pinfunction "GND_AF26") (pintype "passive"))
      (node (ref "U11") (pin "B13") (pinfunction "GND_B13") (pintype "passive"))
      (node (ref "U11") (pin "B17") (pinfunction "GND_B17") (pintype "passive"))
      (node (ref "U11") (pin "B21") (pinfunction "GND_B21") (pintype "passive"))
      (node (ref "U11") (pin "B5") (pinfunction "GND_B5") (pintype "passive"))
      (node (ref "U11") (pin "B9") (pinfunction "GND_B9") (pintype "passive"))
      (node (ref "U11") (pin "D4") (pinfunction "GND_D4") (pintype "passive"))
      (node (ref "U11") (pin "E11") (pinfunction "GND_E11") (pintype "passive"))
      (node (ref "U11") (pin "E15") (pinfunction "GND_E15") (pintype "passive"))
      (node (ref "U11") (pin "E22") (pinfunction "GND_E22") (pintype "passive"))
      (node (ref "U11") (pin "E7") (pinfunction "GND_E7") (pintype "passive"))
      (node (ref "U11") (pin "F19") (pinfunction "GND_F19") (pintype "passive"))
      (node (ref "U11") (pin "F2") (pinfunction "GND_F2") (pintype "passive"))
      (node (ref "U11") (pin "F25") (pinfunction "GND_F25") (pintype "passive"))
      (node (ref "U11") (pin "H11") (pinfunction "GND_H11") (pintype "passive"))
      (node (ref "U11") (pin "H23") (pinfunction "GND_H23") (pintype "passive"))
      (node (ref "U11") (pin "H4") (pinfunction "GND_H4") (pintype "passive"))
      (node (ref "U11") (pin "J19") (pinfunction "GND_J19") (pintype "passive"))
      (node (ref "U11") (pin "J8") (pinfunction "GND_J8") (pintype "passive"))
      (node (ref "U11") (pin "K16") (pinfunction "GND_K16") (pintype "passive"))
      (node (ref "U11") (pin "K2") (pinfunction "GND_K2") (pintype "passive"))
      (node (ref "U11") (pin "K25") (pinfunction "GND_K25") (pintype "passive"))
      (node (ref "U11") (pin "L11") (pinfunction "GND_L11") (pintype "passive"))
      (node (ref "U11") (pin "L13") (pinfunction "GND_L13") (pintype "passive"))
      (node (ref "U11") (pin "L15") (pinfunction "GND_L15") (pintype "passive"))
      (node (ref "U11") (pin "M12") (pinfunction "GND_M12") (pintype "passive"))
      (node (ref "U11") (pin "M14") (pinfunction "GND_M14") (pintype "passive"))
      (node (ref "U11") (pin "M16") (pinfunction "GND_M16") (pintype "passive"))
      (node (ref "U11") (pin "M22") (pinfunction "GND_M22") (pintype "passive"))
      (node (ref "U11") (pin "M5") (pinfunction "GND_M5") (pintype "passive"))
      (node (ref "U11") (pin "N11") (pinfunction "GND_N11") (pintype "passive"))
      (node (ref "U11") (pin "N13") (pinfunction "GND_N13") (pintype "passive"))
      (node (ref "U11") (pin "N15") (pinfunction "GND_N15") (pintype "passive"))
      (node (ref "U11") (pin "P12") (pinfunction "GND_P12") (pintype "passive"))
      (node (ref "U11") (pin "P14") (pinfunction "GND_P14") (pintype "passive"))
      (node (ref "U11") (pin "P16") (pinfunction "GND_P16") (pintype "passive"))
      (node (ref "U11") (pin "P19") (pinfunction "GND_P19") (pintype "passive"))
      (node (ref "U11") (pin "P2") (pinfunction "GND_P2") (pintype "passive"))
      (node (ref "U11") (pin "P25") (pinfunction "GND_P25") (pintype "passive"))
      (node (ref "U11") (pin "R11") (pinfunction "GND_R11") (pintype "passive"))
      (node (ref "U11") (pin "R13") (pinfunction "GND_R13") (pintype "passive"))
      (node (ref "U11") (pin "R15") (pinfunction "GND_R15") (pintype "passive"))
      (node (ref "U11") (pin "R8") (pinfunction "GND_R8") (pintype "passive"))
      (node (ref "U11") (pin "T12") (pinfunction "GND_T12") (pintype "passive"))
      (node (ref "U11") (pin "T14") (pinfunction "GND_T14") (pintype "passive"))
      (node (ref "U11") (pin "T16") (pinfunction "GND_T16") (pintype "passive"))
      (node (ref "U11") (pin "T21") (pinfunction "GND_T21") (pintype "passive"))
      (node (ref "U11") (pin "T5") (pinfunction "GND_T5") (pintype "passive"))
      (node (ref "U11") (pin "U11") (pinfunction "GND_U11") (pintype "passive"))
      (node (ref "U11") (pin "V2") (pinfunction "GND_V2") (pintype "passive"))
      (node (ref "U11") (pin "V25") (pinfunction "GND_V25") (pintype "passive"))
      (node (ref "U11") (pin "W15") (pinfunction "GND_W15") (pintype "passive"))
      (node (ref "U11") (pin "W20") (pinfunction "GND_W20") (pintype "passive"))
      (node (ref "U11") (pin "Y11") (pinfunction "GND_Y11") (pintype "passive"))
      (node (ref "U11") (pin "Y23") (pinfunction "GND_Y23") (pintype "passive"))
      (node (ref "U11") (pin "Y4") (pinfunction "GND_Y4") (pintype "passive"))
      (node (ref "U11") (pin "Y7") (pinfunction "GND_Y7") (pintype "passive"))
    )
    (net (code "5") (name "unconnected-(U11J-NC-PadE12)") (class "Default")
      (node (ref "U11") (pin "E12") (pinfunction "NC_E12") (pintype "passive+no_connect"))
    )
    (net (code "6") (name "unconnected-(U11J-NC-PadF8)") (class "Default")
      (node (ref "U11") (pin "F8") (pinfunction "NC_F8") (pintype "passive+no_connect"))
    )
    (net (code "7") (name "unconnected-(U11J-NC-PadF12)") (class "Default")
      (node (ref "U11") (pin "F12") (pinfunction "NC_F12") (pintype "passive+no_connect"))
    )
    (net (code "8") (name "unconnected-(U11J-NC-PadF14)") (class "Default")
      (node (ref "U11") (pin "F14") (pinfunction "NC_F14") (pintype "passive+no_connect"))
    )
    (net (code "9") (name "unconnected-(U11J-NC-PadG9)") (class "Default")
      (node (ref "U11") (pin "G9") (pinfunction "NC_G9") (pintype "passive+no_connect"))
    )
    (net (code "10") (name "unconnected-(U11J-NC-PadG11)") (class "Default")
      (node (ref "U11") (pin "G11") (pinfunction "NC_G11") (pintype "passive+no_connect"))
    )
    (net (code "11") (name "unconnected-(U11J-NC-PadG13)") (class "Default")
      (node (ref "U11") (pin "G13") (pinfunction "NC_G13") (pintype "passive+no_connect"))
    )
    (net (code "12") (name "unconnected-(U11J-NC-PadH9)") (class "Default")
      (node (ref "U11") (pin "H9") (pinfunction "NC_H9") (pintype "passive+no_connect"))
    )
    (net (code "13") (name "unconnected-(U11J-NC-PadH10)") (class "Default")
      (node (ref "U11") (pin "H10") (pinfunction "NC_H10") (pintype "passive+no_connect"))
    )
    (net (code "14") (name "unconnected-(U11J-NC-PadH12)") (class "Default")
      (node (ref "U11") (pin "H12") (pinfunction "NC_H12") (pintype "passive+no_connect"))
    )
    (net (code "15") (name "unconnected-(U11J-NC-PadH13)") (class "Default")
      (node (ref "U11") (pin "H13") (pinfunction "NC_H13") (pintype "passive+no_connect"))
    )
    (net (code "16") (name "unconnected-(U11J-NC-PadJ11)") (class "Default")
      (node (ref "U11") (pin "J11") (pinfunction "NC_J11") (pintype "passive+no_connect"))
    )
    (net (code "17") (name "unconnected-(U11J-NC-PadJ12)") (class "Default")
      (node (ref "U11") (pin "J12") (pinfunction "NC_J12") (pintype "passive+no_connect"))
    )
    (net (code "18") (name "unconnected-(U11J-NC-PadJ13)") (class "Default")
      (node (ref "U11") (pin "J13") (pinfunction "NC_J13") (pintype "passive+no_connect"))
    )
    (net (code "19") (name "unconnected-(U11J-NC-PadJ16)") (class "Default")
      (node (ref "U11") (pin "J16") (pinfunction "NC_J16") (pintype "passive+no_connect"))
    )
    (net (code "20") (name "unconnected-(U11J-NC-PadK12)") (class "Default")
      (node (ref "U11") (pin "K12") (pinfunction "NC_K12") (pintype "passive+no_connect"))
    )
    (net (code "21") (name "unconnected-(U11J-NC-PadK14)") (class "Default")
      (node (ref "U11") (pin "K14") (pinfunction "NC_K14") (pintype "passive+no_connect"))
    )
    (net (code "22") (name "unconnected-(U11J-NC-PadK15)") (class "Default")
      (node (ref "U11") (pin "K15") (pinfunction "NC_K15") (pintype "passive+no_connect"))
    )
  )
)
